# Sheet1.net
KiCad netlist of a schematic drawn in Altium Designer
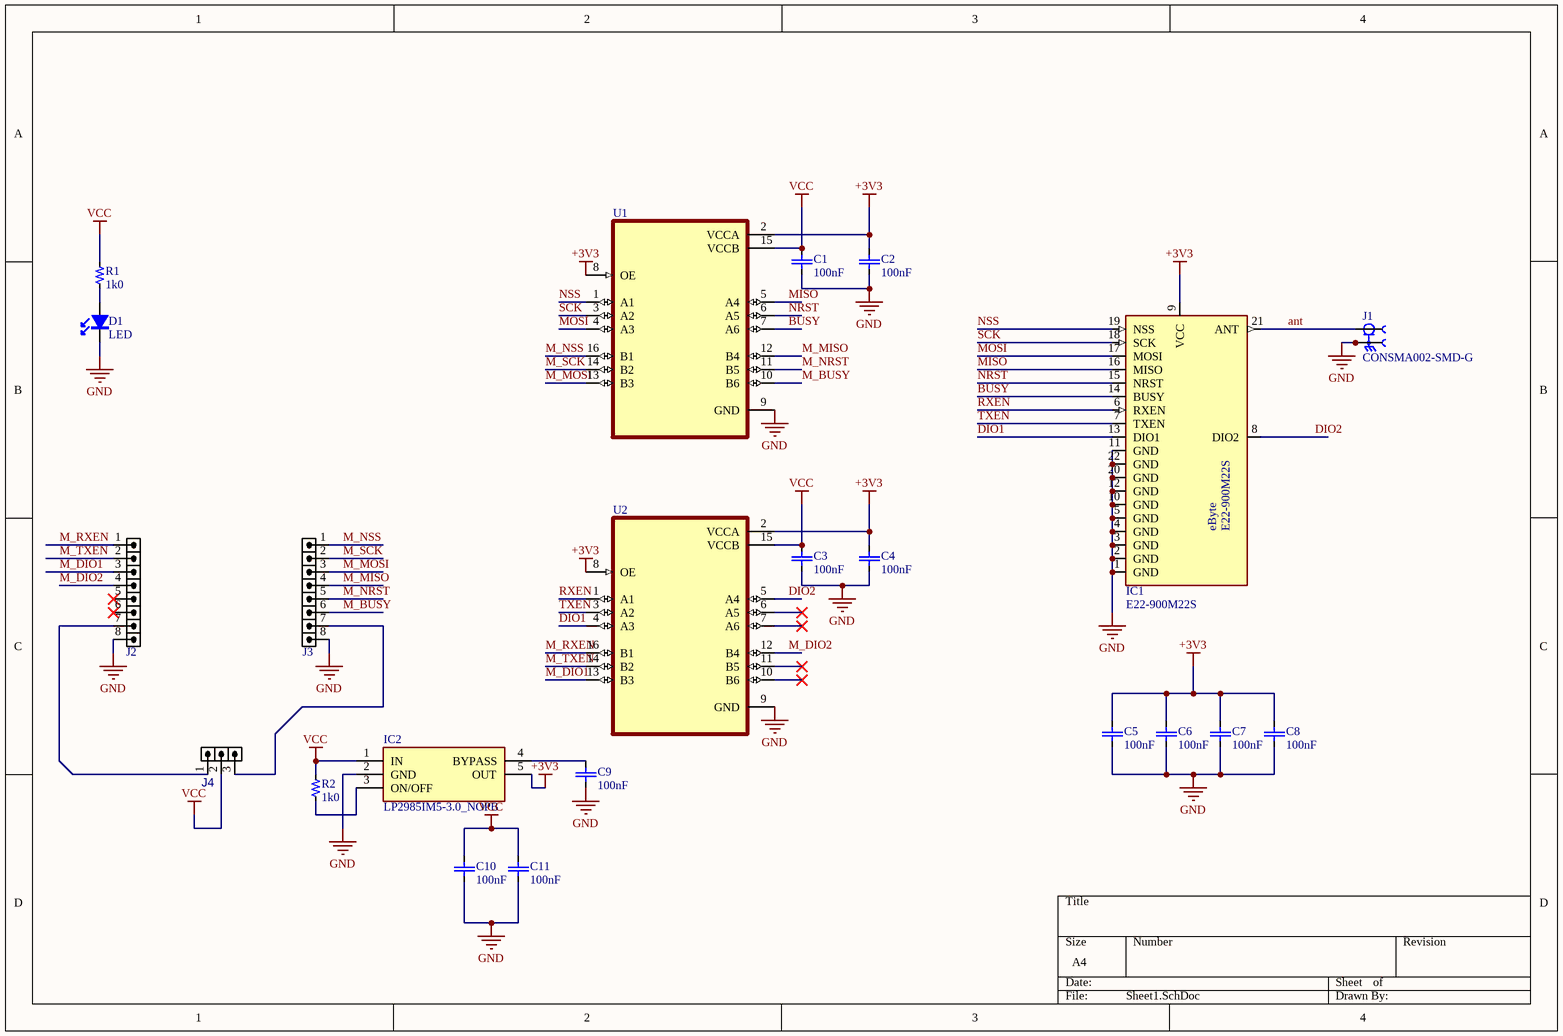
[diagram p0: Sheet1.SchDoc]

(export (version "E")
  (design (tool "Eeschema 10.0.6"))
  (components
    (comp (ref "C1")
      (value "100nF")
      (footprint "C0805")
      (description "Capacitor without polarity")
      (fields (field (name "VOLTAGE") "25V"))
      (libsource (lib "RasUNMSM") (part "Capacitor"))
    )
    (comp (ref "C2")
      (value "100nF")
      (footprint "C0805")
      (description "Capacitor without polarity")
      (fields (field (name "VOLTAGE") "25V"))
      (libsource (lib "RasUNMSM") (part "Capacitor"))
    )
    (comp (ref "C3")
      (value "100nF")
      (footprint "C0805")
      (description "Capacitor without polarity")
      (fields (field (name "VOLTAGE") "25V"))
      (libsource (lib "RasUNMSM") (part "Capacitor"))
    )
    (comp (ref "C4")
      (value "100nF")
      (footprint "C0805")
      (description "Capacitor without polarity")
      (fields (field (name "VOLTAGE") "25V"))
      (libsource (lib "RasUNMSM") (part "Capacitor"))
    )
    (comp (ref "C5")
      (value "100nF")
      (footprint "C0805")
      (description "Capacitor without polarity")
      (fields (field (name "VOLTAGE") "25V"))
      (libsource (lib "RasUNMSM") (part "Capacitor"))
    )
    (comp (ref "C6")
      (value "100nF")
      (footprint "C0805")
      (description "Capacitor without polarity")
      (fields (field (name "VOLTAGE") "25V"))
      (libsource (lib "RasUNMSM") (part "Capacitor"))
    )
    (comp (ref "C7")
      (value "100nF")
      (footprint "C0805")
      (description "Capacitor without polarity")
      (fields (field (name "VOLTAGE") "25V"))
      (libsource (lib "RasUNMSM") (part "Capacitor"))
    )
    (comp (ref "C8")
      (value "100nF")
      (footprint "C0805")
      (description "Capacitor without polarity")
      (fields (field (name "VOLTAGE") "25V"))
      (libsource (lib "RasUNMSM") (part "Capacitor"))
    )
    (comp (ref "C9")
      (value "100nF")
      (footprint "C0805")
      (description "Capacitor without polarity")
      (fields (field (name "VOLTAGE") "25V"))
      (libsource (lib "RasUNMSM") (part "Capacitor"))
    )
    (comp (ref "C10")
      (value "100nF")
      (footprint "C0805")
      (description "Capacitor without polarity")
      (fields (field (name "VOLTAGE") "25V"))
      (libsource (lib "RasUNMSM") (part "Capacitor"))
    )
    (comp (ref "C11")
      (value "100nF")
      (footprint "C0805")
      (description "Capacitor without polarity")
      (fields (field (name "VOLTAGE") "25V"))
      (libsource (lib "RasUNMSM") (part "Capacitor"))
    )
    (comp (ref "D1")
      (value "LED")
      (footprint "LED-0805")
      (description "LED - Light-Emitting Diode")
      (libsource (lib "RasUNMSM") (part "LED"))
    )
    (comp (ref "IC1")
      (value "E22-900M22S")
      (footprint "E22-900M22S")
      (description "SX1262 868/915MHz SPI SMD LoRa Module")
      (fields (field (name "MF") "EBYTE"))
      (libsource (lib "E22-900M22S") (part "E22-900M22S"))
    )
    (comp (ref "IC2")
      (value "LP2985IM5-3.0_NOPB")
      (footprint "SamacSys:SOT95P280X145-5N")
      (description "Integrated Circuit")
      (fields
        (field (name "MANUFACTURER_PART_NUMBER") "LP2985IM5-3.0/NOPB")
        (field (name "MOUSER PART NUMBER") "926-LP2985IM53.0NOPB")
      )
      (libsource (lib "*") (part "LP2985IM5-3.0_NOPB"))
    )
    (comp (ref "J1")
      (value "CONSMA002-SMD-G")
      (footprint "LINX_CONSMA002-SMD-G")
      (description "SMA Female Right-Angle Surface-Mount Connector, Gold")
      (fields (field (name "MF") "Linx Technologies"))
      (libsource (lib "CONSMA002-SMD-G") (part "CONSMA002-SMD-G"))
    )
    (comp (ref "J2")
      (value "HDR1X8")
      (footprint "HDR_M_1X8")
      (description "CONN, HEADER, Male, pitch: 2.54mm, 8POS")
      (libsource (lib "") (part "Header Male THT 1x8_1"))
    )
    (comp (ref "J3")
      (value "HDR1X8")
      (footprint "HDR_M_1X8")
      (description "CONN, HEADER, Male, pitch: 2.54mm, 8POS")
      (libsource (lib "Headers") (part "Header Male THT 1x8"))
    )
    (comp (ref "J4")
      (value "HDRM3")
      (footprint "HDRS_M_1X3")
      (description "CONN, HEADER, Male, pitch: 2.54mm, 3POS, SMD")
      (fields (field (name "MANF_P#") "87898-0304") (field (name "MANF") "MOLEX"))
      (libsource (lib "Headers") (part "Header Male 1x3 smd"))
    )
    (comp (ref "R1")
      (value "1k0")
      (footprint "R0805")
      (description "Single resistor")
      (fields (field (name "POWER") "0.125W"))
      (libsource (lib "RasUNMSM") (part "Resistor"))
    )
    (comp (ref "R2")
      (value "1k0")
      (footprint "R0805")
      (description "Single resistor")
      (fields (field (name "POWER") "0.125W"))
      (libsource (lib "RasUNMSM") (part "Resistor"))
    )
    (comp (ref "U1")
      (value "TXB0106PWR")
      (footprint "SOP65P640X120-16N")
      (fields
        (field (name "MF") "Texas Instruments")
        (field (name "BUYPART") "https://www.snapeda.com/parts/TXB0106PWR/Texas%20Instruments/view-part/134340/?ref=eda")
      )
      (libsource (lib "TXB0106PWR") (part "TXB0106PWR"))
    )
    (comp (ref "U2")
      (value "TXB0106PWR")
      (footprint "SOP65P640X120-16N")
      (fields
        (field (name "MF") "Texas Instruments")
        (field (name "BUYPART") "https://www.snapeda.com/parts/TXB0106PWR/Texas%20Instruments/view-part/134340/?ref=eda")
      )
      (libsource (lib "TXB0106PWR") (part "TXB0106PWR"))
    )
  )
  (nets
    (net (code "1") (name "+3V3") (class "Default")
      (node (ref "C2") (pin "2") (pinfunction "2_2") (pintype "passive"))
      (node (ref "C4") (pin "2") (pinfunction "2_2") (pintype "passive"))
      (node (ref "C5") (pin "2") (pinfunction "2_2") (pintype "passive"))
      (node (ref "C6") (pin "2") (pinfunction "2_2") (pintype "passive"))
      (node (ref "C7") (pin "2") (pinfunction "2_2") (pintype "passive"))
      (node (ref "C8") (pin "2") (pinfunction "2_2") (pintype "passive"))
      (node (ref "IC1") (pin "9") (pinfunction "VCC_9") (pintype "power_in"))
      (node (ref "IC2") (pin "5") (pinfunction "OUT_5") (pintype "passive"))
      (node (ref "U1") (pin "2") (pinfunction "VCCA_2") (pintype "power_in"))
      (node (ref "U1") (pin "8") (pinfunction "OE_8") (pintype "input"))
      (node (ref "U2") (pin "2") (pinfunction "VCCA_2") (pintype "power_in"))
      (node (ref "U2") (pin "8") (pinfunction "OE_8") (pintype "input"))
    )
    (net (code "2") (name "/BUSY") (class "Default")
      (node (ref "IC1") (pin "14") (pinfunction "BUSY_14") (pintype "bidirectional"))
      (node (ref "U1") (pin "7") (pinfunction "A6_7") (pintype "bidirectional"))
    )
    (net (code "3") (name "/DIO1") (class "Default")
      (node (ref "IC1") (pin "13") (pinfunction "DIO1_13") (pintype "bidirectional"))
      (node (ref "U2") (pin "4") (pinfunction "A3_4") (pintype "bidirectional"))
    )
    (net (code "4") (name "/DIO2") (class "Default")
      (node (ref "IC1") (pin "8") (pinfunction "DIO2_8") (pintype "bidirectional"))
      (node (ref "U2") (pin "5") (pinfunction "A4_5") (pintype "bidirectional"))
    )
    (net (code "5") (name "/MISO") (class "Default")
      (node (ref "IC1") (pin "16") (pinfunction "MISO_16") (pintype "bidirectional"))
      (node (ref "U1") (pin "5") (pinfunction "A4_5") (pintype "bidirectional"))
    )
    (net (code "6") (name "/MOSI") (class "Default")
      (node (ref "IC1") (pin "17") (pinfunction "MOSI_17") (pintype "bidirectional"))
      (node (ref "U1") (pin "4") (pinfunction "A3_4") (pintype "bidirectional"))
    )
    (net (code "7") (name "/M_BUSY") (class "Default")
      (node (ref "J3") (pin "6") (pinfunction "6_6") (pintype "passive"))
      (node (ref "U1") (pin "10") (pinfunction "B6_10") (pintype "bidirectional"))
    )
    (net (code "8") (name "/M_DIO1") (class "Default")
      (node (ref "J2") (pin "3") (pinfunction "3_3") (pintype "passive"))
      (node (ref "U2") (pin "13") (pinfunction "B3_13") (pintype "bidirectional"))
    )
    (net (code "9") (name "/M_DIO2") (class "Default")
      (node (ref "J2") (pin "4") (pinfunction "4_4") (pintype "passive"))
      (node (ref "U2") (pin "12") (pinfunction "B4_12") (pintype "bidirectional"))
    )
    (net (code "10") (name "/M_MISO") (class "Default")
      (node (ref "J3") (pin "4") (pinfunction "4_4") (pintype "passive"))
      (node (ref "U1") (pin "12") (pinfunction "B4_12") (pintype "bidirectional"))
    )
    (net (code "11") (name "/M_MOSI") (class "Default")
      (node (ref "J3") (pin "3") (pinfunction "3_3") (pintype "passive"))
      (node (ref "U1") (pin "13") (pinfunction "B3_13") (pintype "bidirectional"))
    )
    (net (code "12") (name "/M_NRST") (class "Default")
      (node (ref "J3") (pin "5") (pinfunction "5_5") (pintype "passive"))
      (node (ref "U1") (pin "11") (pinfunction "B5_11") (pintype "bidirectional"))
    )
    (net (code "13") (name "/M_NSS") (class "Default")
      (node (ref "J3") (pin "1") (pinfunction "1_1") (pintype "passive"))
      (node (ref "U1") (pin "16") (pinfunction "B1_16") (pintype "bidirectional"))
    )
    (net (code "14") (name "/M_RXEN") (class "Default")
      (node (ref "J2") (pin "1") (pinfunction "1_1") (pintype "passive"))
      (node (ref "U2") (pin "16") (pinfunction "B1_16") (pintype "bidirectional"))
    )
    (net (code "15") (name "/M_SCK") (class "Default")
      (node (ref "J3") (pin "2") (pinfunction "2_2") (pintype "passive"))
      (node (ref "U1") (pin "14") (pinfunction "B2_14") (pintype "bidirectional"))
    )
    (net (code "16") (name "/M_TXEN") (class "Default")
      (node (ref "J2") (pin "2") (pinfunction "2_2") (pintype "passive"))
      (node (ref "U2") (pin "14") (pinfunction "B2_14") (pintype "bidirectional"))
    )
    (net (code "17") (name "/NRST") (class "Default")
      (node (ref "IC1") (pin "15") (pinfunction "NRST_15") (pintype "bidirectional"))
      (node (ref "U1") (pin "6") (pinfunction "A5_6") (pintype "bidirectional"))
    )
    (net (code "18") (name "/NSS") (class "Default")
      (node (ref "IC1") (pin "19") (pinfunction "NSS_19") (pintype "input"))
      (node (ref "U1") (pin "1") (pinfunction "A1_1") (pintype "bidirectional"))
    )
    (net (code "19") (name "/RXEN") (class "Default")
      (node (ref "IC1") (pin "6") (pinfunction "RXEN_6") (pintype "input"))
      (node (ref "U2") (pin "1") (pinfunction "A1_1") (pintype "bidirectional"))
    )
    (net (code "20") (name "/SCK") (class "Default")
      (node (ref "IC1") (pin "18") (pinfunction "SCK_18") (pintype "input"))
      (node (ref "U1") (pin "3") (pinfunction "A2_3") (pintype "bidirectional"))
    )
    (net (code "21") (name "/TXEN") (class "Default")
      (node (ref "IC1") (pin "7") (pinfunction "TXEN_7") (pintype "bidirectional"))
      (node (ref "U2") (pin "3") (pinfunction "A2_3") (pintype "bidirectional"))
    )
    (net (code "22") (name "/ant") (class "Default")
      (node (ref "IC1") (pin "21") (pinfunction "ANT_21") (pintype "output"))
      (node (ref "J1") (pin "1") (pinfunction "1_1") (pintype "passive"))
    )
    (net (code "23") (name "GND") (class "Default")
      (node (ref "C1") (pin "1") (pinfunction "1_1") (pintype "passive"))
      (node (ref "C10") (pin "1") (pinfunction "1_1") (pintype "passive"))
      (node (ref "C11") (pin "1") (pinfunction "1_1") (pintype "passive"))
      (node (ref "C2") (pin "1") (pinfunction "1_1") (pintype "passive"))
      (node (ref "C3") (pin "1") (pinfunction "1_1") (pintype "passive"))
      (node (ref "C4") (pin "1") (pinfunction "1_1") (pintype "passive"))
      (node (ref "C5") (pin "1") (pinfunction "1_1") (pintype "passive"))
      (node (ref "C6") (pin "1") (pinfunction "1_1") (pintype "passive"))
      (node (ref "C7") (pin "1") (pinfunction "1_1") (pintype "passive"))
      (node (ref "C8") (pin "1") (pinfunction "1_1") (pintype "passive"))
      (node (ref "C9") (pin "1") (pinfunction "1_1") (pintype "passive"))
      (node (ref "D1") (pin "1") (pinfunction "1_1") (pintype "passive"))
      (node (ref "IC1") (pin "1") (pinfunction "GND_1") (pintype "power_in"))
      (node (ref "IC1") (pin "10") (pinfunction "GND_10") (pintype "power_in"))
      (node (ref "IC1") (pin "11") (pinfunction "GND_11") (pintype "power_in"))
      (node (ref "IC1") (pin "12") (pinfunction "GND_12") (pintype "power_in"))
      (node (ref "IC1") (pin "2") (pinfunction "GND_2") (pintype "power_in"))
      (node (ref "IC1") (pin "20") (pinfunction "GND_20") (pintype "power_in"))
      (node (ref "IC1") (pin "22") (pinfunction "GND_22") (pintype "power_in"))
      (node (ref "IC1") (pin "3") (pinfunction "GND_3") (pintype "power_in"))
      (node (ref "IC1") (pin "4") (pinfunction "GND_4") (pintype "power_in"))
      (node (ref "IC1") (pin "5") (pinfunction "GND_5") (pintype "power_in"))
      (node (ref "IC2") (pin "2") (pinfunction "GND_2") (pintype "passive"))
      (node (ref "J1") (pin "S1") (pinfunction "2_S1") (pintype "passive"))
      (node (ref "J1") (pin "S2") (pinfunction "2_S2") (pintype "passive"))
      (node (ref "J2") (pin "8") (pinfunction "8_8") (pintype "passive"))
      (node (ref "J3") (pin "8") (pinfunction "8_8") (pintype "passive"))
      (node (ref "U1") (pin "9") (pinfunction "GND_9") (pintype "power_in"))
      (node (ref "U2") (pin "9") (pinfunction "GND_9") (pintype "power_in"))
    )
    (net (code "24") (name "Net-(D1-Pad2)") (class "Default")
      (node (ref "D1") (pin "2") (pinfunction "2_2") (pintype "passive"))
      (node (ref "R1") (pin "1") (pinfunction "1_1") (pintype "passive"))
    )
    (net (code "25") (name "Net-(IC2-BYPASS)") (class "Default")
      (node (ref "C9") (pin "2") (pinfunction "2_2") (pintype "passive"))
      (node (ref "IC2") (pin "4") (pinfunction "BYPASS_4") (pintype "passive"))
    )
    (net (code "26") (name "Net-(IC2-ON{slash}OFF)") (class "Default")
      (node (ref "IC2") (pin "3") (pinfunction "ON/OFF_3") (pintype "passive"))
      (node (ref "R2") (pin "1") (pinfunction "1_1") (pintype "passive"))
    )
    (net (code "27") (name "Net-(J3-Pad7)") (class "Default")
      (node (ref "J3") (pin "7") (pinfunction "7_7") (pintype "passive"))
      (node (ref "J4") (pin "3") (pinfunction "3_3") (pintype "passive"))
    )
    (net (code "28") (name "Net-(J4-P1)") (class "Default")
      (node (ref "J2") (pin "7") (pinfunction "7_7") (pintype "passive"))
      (node (ref "J4") (pin "1") (pinfunction "P1_1") (pintype "passive"))
    )
    (net (code "29") (name "VCC") (class "Default")
      (node (ref "C1") (pin "2") (pinfunction "2_2") (pintype "passive"))
      (node (ref "C10") (pin "2") (pinfunction "2_2") (pintype "passive"))
      (node (ref "C11") (pin "2") (pinfunction "2_2") (pintype "passive"))
      (node (ref "C3") (pin "2") (pinfunction "2_2") (pintype "passive"))
      (node (ref "IC2") (pin "1") (pinfunction "IN_1") (pintype "passive"))
      (node (ref "J4") (pin "2") (pinfunction "P2_2") (pintype "passive"))
      (node (ref "R1") (pin "2") (pinfunction "2_2") (pintype "passive"))
      (node (ref "R2") (pin "2") (pinfunction "2_2") (pintype "passive"))
      (node (ref "U1") (pin "15") (pinfunction "VCCB_15") (pintype "power_in"))
      (node (ref "U2") (pin "15") (pinfunction "VCCB_15") (pintype "power_in"))
    )
    (net (code "30") (name "unconnected-(J2-Pad5)") (class "Default")
      (node (ref "J2") (pin "5") (pinfunction "5_5") (pintype "passive+no_connect"))
    )
    (net (code "31") (name "unconnected-(J2-Pad6)") (class "Default")
      (node (ref "J2") (pin "6") (pinfunction "6_6") (pintype "passive+no_connect"))
    )
    (net (code "32") (name "unconnected-(U2-A5-Pad6)") (class "Default")
      (node (ref "U2") (pin "6") (pinfunction "A5_6") (pintype "bidirectional+no_connect"))
    )
    (net (code "33") (name "unconnected-(U2-A6-Pad7)") (class "Default")
      (node (ref "U2") (pin "7") (pinfunction "A6_7") (pintype "bidirectional+no_connect"))
    )
    (net (code "34") (name "unconnected-(U2-B5-Pad11)") (class "Default")
      (node (ref "U2") (pin "11") (pinfunction "B5_11") (pintype "bidirectional+no_connect"))
    )
    (net (code "35") (name "unconnected-(U2-B6-Pad10)") (class "Default")
      (node (ref "U2") (pin "10") (pinfunction "B6_10") (pintype "bidirectional+no_connect"))
    )
  )
)
